# sch_arduboy.net
KiCad netlist of a schematic drawn in Altium Designer
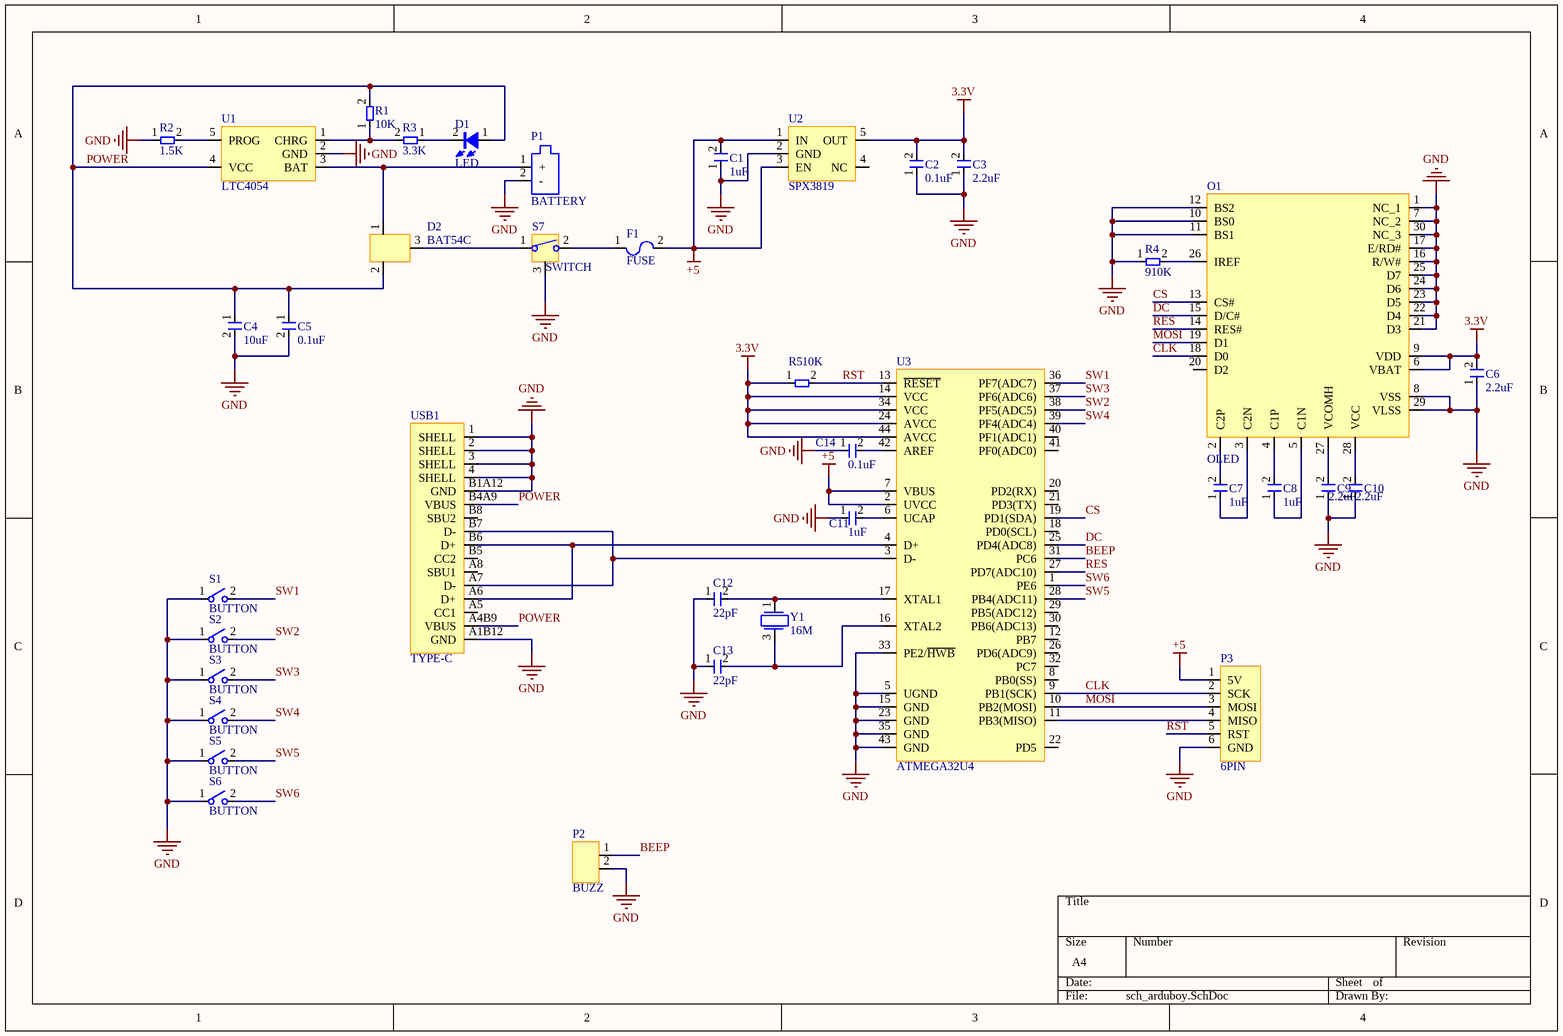
[diagram p0: sch_arduboy.SchDoc]

(export (version "E")
  (design (tool "Eeschema 10.0.6"))
  (components
    (comp (ref "C1")
      (value "1uF")
      (footprint "CAP0603")
      (description "CAP")
      (libsource (lib "arduboy_schlib") (part "CAP"))
    )
    (comp (ref "C2")
      (value "0.1uF")
      (footprint "CAP0603")
      (description "CAP")
      (libsource (lib "arduboy_schlib") (part "CAP"))
    )
    (comp (ref "C3")
      (value "2.2uF")
      (footprint "CAP0603")
      (description "CAP")
      (libsource (lib "arduboy_schlib") (part "CAP"))
    )
    (comp (ref "C4")
      (value "10uF")
      (footprint "10uFCAP3216")
      (description "CAP")
      (libsource (lib "arduboy_schlib") (part "CAP"))
    )
    (comp (ref "C5")
      (value "0.1uF")
      (footprint "CAP0603")
      (description "CAP")
      (libsource (lib "arduboy_schlib") (part "CAP"))
    )
    (comp (ref "C6")
      (value "2.2uF")
      (footprint "CAP0603")
      (description "CAP")
      (libsource (lib "arduboy_schlib") (part "CAP"))
    )
    (comp (ref "C7")
      (value "1uF")
      (footprint "CAP0603")
      (description "CAP")
      (libsource (lib "arduboy_schlib") (part "CAP"))
    )
    (comp (ref "C8")
      (value "1uF")
      (footprint "CAP0603")
      (description "CAP")
      (libsource (lib "arduboy_schlib") (part "CAP"))
    )
    (comp (ref "C9")
      (value "2.2uF")
      (footprint "CAP0603")
      (description "CAP")
      (libsource (lib "arduboy_schlib") (part "CAP"))
    )
    (comp (ref "C10")
      (value "2.2uF")
      (footprint "CAP0603")
      (description "CAP")
      (libsource (lib "arduboy_schlib") (part "CAP"))
    )
    (comp (ref "C11")
      (value "1uF")
      (footprint "CAP0603")
      (description "CAP")
      (libsource (lib "arduboy_schlib") (part "CAP"))
    )
    (comp (ref "C12")
      (value "22pF")
      (footprint "CAP0603")
      (description "CAP")
      (libsource (lib "arduboy_schlib") (part "CAP"))
    )
    (comp (ref "C13")
      (value "22pF")
      (footprint "CAP0603")
      (description "CAP")
      (libsource (lib "arduboy_schlib") (part "CAP"))
    )
    (comp (ref "C14")
      (value "0.1uF")
      (footprint "CAP0603")
      (description "CAP")
      (libsource (lib "arduboy_schlib") (part "CAP"))
    )
    (comp (ref "D1") (value "LED") (footprint "LED0603") (libsource (lib "arduboy_schlib") (part "LED")))
    (comp (ref "D2")
      (value "BAT54C")
      (footprint "BAT54CSOT23-3")
      (libsource (lib "arduboy_schlib") (part "BAT54C"))
    )
    (comp (ref "F1") (value "FUSE") (footprint "FUSE1206") (libsource (lib "arduboy_schlib") (part "FUSE")))
    (comp (ref "O1")
      (value "OLED")
      (footprint "OLED30P")
      (description "0.96 128x64OLED")
      (libsource (lib "arduboy_schlib") (part "OLED"))
    )
    (comp (ref "P1")
      (value "BATTERY")
      (footprint "BATTERY")
      (libsource (lib "arduboy_schlib") (part "BATTERY"))
    )
    (comp (ref "P2") (value "BUZZ") (footprint "BUZZ") (libsource (lib "arduboy_schlib") (part "BUZZ")))
    (comp (ref "P3") (value "6PIN") (footprint "6PIN254") (libsource (lib "arduboy_schlib") (part "6PIN")))
    (comp (ref "R1")
      (value "10K")
      (footprint "RES0805")
      (description "电阻")
      (libsource (lib "arduboy_schlib") (part "RES"))
    )
    (comp (ref "R2")
      (value "1.5K")
      (footprint "RES0805")
      (description "电阻")
      (libsource (lib "arduboy_schlib") (part "RES"))
    )
    (comp (ref "R3")
      (value "3.3K")
      (footprint "RES0805")
      (description "电阻")
      (libsource (lib "arduboy_schlib") (part "RES"))
    )
    (comp (ref "R4")
      (value "910K")
      (footprint "RES0805")
      (description "电阻")
      (libsource (lib "arduboy_schlib") (part "RES"))
    )
    (comp (ref "R5")
      (value "10K")
      (footprint "RES0805")
      (description "电阻")
      (libsource (lib "arduboy_schlib") (part "RES"))
    )
    (comp (ref "S1")
      (value "BUTTON")
      (footprint "SKP_BUTTON")
      (libsource (lib "arduboy_schlib") (part "BUTTON"))
    )
    (comp (ref "S2")
      (value "BUTTON")
      (footprint "SKP_BUTTON")
      (libsource (lib "arduboy_schlib") (part "BUTTON"))
    )
    (comp (ref "S3")
      (value "BUTTON")
      (footprint "SKP_BUTTON")
      (libsource (lib "arduboy_schlib") (part "BUTTON"))
    )
    (comp (ref "S4")
      (value "BUTTON")
      (footprint "SKP_BUTTON")
      (libsource (lib "arduboy_schlib") (part "BUTTON"))
    )
    (comp (ref "S5")
      (value "BUTTON")
      (footprint "SKP_BUTTON")
      (libsource (lib "arduboy_schlib") (part "BUTTON"))
    )
    (comp (ref "S6")
      (value "BUTTON")
      (footprint "SKP_BUTTON")
      (libsource (lib "arduboy_schlib") (part "BUTTON"))
    )
    (comp (ref "S7")
      (value "SWITCH")
      (footprint "SWITCH_BUTTON")
      (libsource (lib "arduboy_schlib") (part "SWITCH"))
    )
    (comp (ref "U1")
      (value "LTC4054")
      (footprint "LTC4054")
      (libsource (lib "arduboy_schlib") (part "LTC4054"))
    )
    (comp (ref "U2")
      (value "SPX3819")
      (footprint "SPX3819")
      (libsource (lib "arduboy_schlib") (part "SPX3819"))
    )
    (comp (ref "U3")
      (value "ATMEGA32U4")
      (footprint "ATMEGA32U4AU")
      (libsource (lib "arduboy_schlib") (part "ATMEGA32U4"))
    )
    (comp (ref "USB1")
      (value "TYPE-C")
      (footprint "TYPE-C")
      (libsource (lib "arduboy_schlib") (part "TYPE-C"))
    )
    (comp (ref "Y1")
      (value "16M")
      (footprint "CRYSTAL")
      (description "CRYSTAL")
      (libsource (lib "arduboy_schlib") (part "CRYSTAL"))
    )
  )
  (nets
    (net (code "1") (name "+5") (class "Default")
      (node (ref "C1") (pin "2") (pinfunction "2_2") (pintype "passive"))
      (node (ref "F1") (pin "2") (pinfunction "2_2") (pintype "passive"))
      (node (ref "P3") (pin "1") (pinfunction "5V_1") (pintype "passive"))
      (node (ref "U2") (pin "1") (pinfunction "IN_1") (pintype "passive"))
      (node (ref "U2") (pin "3") (pinfunction "EN_3") (pintype "passive"))
      (node (ref "U3") (pin "2") (pinfunction "UVCC_2") (pintype "passive"))
      (node (ref "U3") (pin "7") (pinfunction "VBUS_7") (pintype "passive"))
    )
    (net (code "2") (name "/BEEP") (class "Default")
      (node (ref "P2") (pin "1") (pinfunction "1_1") (pintype "passive"))
      (node (ref "U3") (pin "31") (pinfunction "PC6_31") (pintype "passive"))
    )
    (net (code "3") (name "/CLK") (class "Default")
      (node (ref "O1") (pin "18") (pinfunction "D0_18") (pintype "passive"))
      (node (ref "P3") (pin "2") (pinfunction "SCK_2") (pintype "passive"))
      (node (ref "U3") (pin "9") (pinfunction "PB1(SCK)_9") (pintype "passive"))
    )
    (net (code "4") (name "/CS") (class "Default")
      (node (ref "O1") (pin "13") (pinfunction "CS#_13") (pintype "passive"))
      (node (ref "U3") (pin "19") (pinfunction "PD1(SDA)_19") (pintype "passive"))
    )
    (net (code "5") (name "/DC") (class "Default")
      (node (ref "O1") (pin "15") (pinfunction "D/C#_15") (pintype "passive"))
      (node (ref "U3") (pin "25") (pinfunction "PD4(ADC8)_25") (pintype "passive"))
    )
    (net (code "6") (name "/MOSI") (class "Default")
      (node (ref "O1") (pin "19") (pinfunction "D1_19") (pintype "passive"))
      (node (ref "P3") (pin "3") (pinfunction "MOSI_3") (pintype "passive"))
      (node (ref "U3") (pin "10") (pinfunction "PB2(MOSI)_10") (pintype "passive"))
    )
    (net (code "7") (name "/POWER") (class "Default")
      (node (ref "C4") (pin "1") (pinfunction "1_1") (pintype "passive"))
      (node (ref "C5") (pin "1") (pinfunction "1_1") (pintype "passive"))
      (node (ref "D1") (pin "1") (pinfunction "1_1") (pintype "passive"))
      (node (ref "D2") (pin "2") (pinfunction "2_2") (pintype "passive"))
      (node (ref "R1") (pin "2") (pinfunction "2_2") (pintype "passive"))
      (node (ref "U1") (pin "4") (pinfunction "VCC_4") (pintype "passive"))
      (node (ref "USB1") (pin "A4B9") (pinfunction "VBUS_A4B9") (pintype "passive"))
      (node (ref "USB1") (pin "B4A9") (pinfunction "VBUS_B4A9") (pintype "passive"))
    )
    (net (code "8") (name "/RES") (class "Default")
      (node (ref "O1") (pin "14") (pinfunction "RES#_14") (pintype "passive"))
      (node (ref "U3") (pin "27") (pinfunction "PD7(ADC10)_27") (pintype "passive"))
    )
    (net (code "9") (name "/RST") (class "Default")
      (node (ref "P3") (pin "5") (pinfunction "RST_5") (pintype "passive"))
      (node (ref "R5") (pin "2") (pinfunction "2_2") (pintype "passive"))
      (node (ref "U3") (pin "13") (pinfunction "~{RESET}_13") (pintype "passive"))
    )
    (net (code "10") (name "/SW1") (class "Default")
      (node (ref "S1") (pin "2") (pinfunction "2_2") (pintype "passive"))
      (node (ref "U3") (pin "36") (pinfunction "PF7(ADC7)_36") (pintype "passive"))
    )
    (net (code "11") (name "/SW2") (class "Default")
      (node (ref "S2") (pin "2") (pinfunction "2_2") (pintype "passive"))
      (node (ref "U3") (pin "38") (pinfunction "PF5(ADC5)_38") (pintype "passive"))
    )
    (net (code "12") (name "/SW3") (class "Default")
      (node (ref "S3") (pin "2") (pinfunction "2_2") (pintype "passive"))
      (node (ref "U3") (pin "37") (pinfunction "PF6(ADC6)_37") (pintype "passive"))
    )
    (net (code "13") (name "/SW4") (class "Default")
      (node (ref "S4") (pin "2") (pinfunction "2_2") (pintype "passive"))
      (node (ref "U3") (pin "39") (pinfunction "PF4(ADC4)_39") (pintype "passive"))
    )
    (net (code "14") (name "/SW5") (class "Default")
      (node (ref "S5") (pin "2") (pinfunction "2_2") (pintype "passive"))
      (node (ref "U3") (pin "28") (pinfunction "PB4(ADC11)_28") (pintype "passive"))
    )
    (net (code "15") (name "/SW6") (class "Default")
      (node (ref "S6") (pin "2") (pinfunction "2_2") (pintype "passive"))
      (node (ref "U3") (pin "1") (pinfunction "PE6_1") (pintype "passive"))
    )
    (net (code "16") (name "3.3V") (class "Default")
      (node (ref "C2") (pin "2") (pinfunction "2_2") (pintype "passive"))
      (node (ref "C3") (pin "2") (pinfunction "2_2") (pintype "passive"))
      (node (ref "C6") (pin "2") (pinfunction "2_2") (pintype "passive"))
      (node (ref "O1") (pin "6") (pinfunction "VBAT_6") (pintype "passive"))
      (node (ref "O1") (pin "9") (pinfunction "VDD_9") (pintype "passive"))
      (node (ref "R5") (pin "1") (pinfunction "1_1") (pintype "passive"))
      (node (ref "U2") (pin "5") (pinfunction "OUT_5") (pintype "passive"))
      (node (ref "U3") (pin "14") (pinfunction "VCC_14") (pintype "passive"))
      (node (ref "U3") (pin "24") (pinfunction "AVCC_24") (pintype "passive"))
      (node (ref "U3") (pin "34") (pinfunction "VCC_34") (pintype "passive"))
      (node (ref "U3") (pin "44") (pinfunction "AVCC_44") (pintype "passive"))
    )
    (net (code "17") (name "GND") (class "Default")
      (node (ref "C1") (pin "1") (pinfunction "1_1") (pintype "passive"))
      (node (ref "C10") (pin "1") (pinfunction "1_1") (pintype "passive"))
      (node (ref "C11") (pin "1") (pinfunction "1_1") (pintype "passive"))
      (node (ref "C12") (pin "1") (pinfunction "1_1") (pintype "passive"))
      (node (ref "C13") (pin "1") (pinfunction "1_1") (pintype "passive"))
      (node (ref "C14") (pin "1") (pinfunction "1_1") (pintype "passive"))
      (node (ref "C2") (pin "1") (pinfunction "1_1") (pintype "passive"))
      (node (ref "C3") (pin "1") (pinfunction "1_1") (pintype "passive"))
      (node (ref "C4") (pin "2") (pinfunction "2_2") (pintype "passive"))
      (node (ref "C5") (pin "2") (pinfunction "2_2") (pintype "passive"))
      (node (ref "C6") (pin "1") (pinfunction "1_1") (pintype "passive"))
      (node (ref "C9") (pin "1") (pinfunction "1_1") (pintype "passive"))
      (node (ref "O1") (pin "1") (pinfunction "NC_1_1") (pintype "passive"))
      (node (ref "O1") (pin "10") (pinfunction "BS0_10") (pintype "passive"))
      (node (ref "O1") (pin "11") (pinfunction "BS1_11") (pintype "passive"))
      (node (ref "O1") (pin "12") (pinfunction "BS2_12") (pintype "passive"))
      (node (ref "O1") (pin "16") (pinfunction "R/W#_16") (pintype "passive"))
      (node (ref "O1") (pin "17") (pinfunction "E/RD#_17") (pintype "passive"))
      (node (ref "O1") (pin "21") (pinfunction "D3_21") (pintype "passive"))
      (node (ref "O1") (pin "22") (pinfunction "D4_22") (pintype "passive"))
      (node (ref "O1") (pin "23") (pinfunction "D5_23") (pintype "passive"))
      (node (ref "O1") (pin "24") (pinfunction "D6_24") (pintype "passive"))
      (node (ref "O1") (pin "25") (pinfunction "D7_25") (pintype "passive"))
      (node (ref "O1") (pin "29") (pinfunction "VLSS_29") (pintype "passive"))
      (node (ref "O1") (pin "30") (pinfunction "NC_3_30") (pintype "passive"))
      (node (ref "O1") (pin "7") (pinfunction "NC_2_7") (pintype "passive"))
      (node (ref "O1") (pin "8") (pinfunction "VSS_8") (pintype "passive"))
      (node (ref "P1") (pin "2") (pinfunction "-_2") (pintype "passive"))
      (node (ref "P2") (pin "2") (pinfunction "2_2") (pintype "passive"))
      (node (ref "P3") (pin "6") (pinfunction "GND_6") (pintype "passive"))
      (node (ref "R2") (pin "1") (pinfunction "1_1") (pintype "passive"))
      (node (ref "R4") (pin "1") (pinfunction "1_1") (pintype "passive"))
      (node (ref "S1") (pin "1") (pinfunction "1_1") (pintype "passive"))
      (node (ref "S2") (pin "1") (pinfunction "1_1") (pintype "passive"))
      (node (ref "S3") (pin "1") (pinfunction "1_1") (pintype "passive"))
      (node (ref "S4") (pin "1") (pinfunction "1_1") (pintype "passive"))
      (node (ref "S5") (pin "1") (pinfunction "1_1") (pintype "passive"))
      (node (ref "S6") (pin "1") (pinfunction "1_1") (pintype "passive"))
      (node (ref "S7") (pin "3") (pinfunction "3_3") (pintype "passive"))
      (node (ref "U1") (pin "2") (pinfunction "GND_2") (pintype "passive"))
      (node (ref "U2") (pin "2") (pinfunction "GND_2") (pintype "passive"))
      (node (ref "U3") (pin "15") (pinfunction "GND_15") (pintype "passive"))
      (node (ref "U3") (pin "23") (pinfunction "GND_23") (pintype "passive"))
      (node (ref "U3") (pin "33") (pinfunction "PE2/~{HWB}_33") (pintype "passive"))
      (node (ref "U3") (pin "35") (pinfunction "GND_35") (pintype "passive"))
      (node (ref "U3") (pin "43") (pinfunction "GND_43") (pintype "passive"))
      (node (ref "U3") (pin "5") (pinfunction "UGND_5") (pintype "passive"))
      (node (ref "USB1") (pin "1") (pinfunction "SHELL_1") (pintype "passive"))
      (node (ref "USB1") (pin "2") (pinfunction "SHELL_2") (pintype "passive"))
      (node (ref "USB1") (pin "3") (pinfunction "SHELL_3") (pintype "passive"))
      (node (ref "USB1") (pin "4") (pinfunction "SHELL_4") (pintype "passive"))
      (node (ref "USB1") (pin "A1B12") (pinfunction "GND_A1B12") (pintype "passive"))
      (node (ref "USB1") (pin "B1A12") (pinfunction "GND_B1A12") (pintype "passive"))
    )
    (net (code "18") (name "Net-(D1-Pad2)") (class "Default")
      (node (ref "D1") (pin "2") (pinfunction "2_2") (pintype "passive"))
      (node (ref "R3") (pin "1") (pinfunction "1_1") (pintype "passive"))
    )
    (net (code "19") (name "Net-(D2-Pad3)") (class "Default")
      (node (ref "D2") (pin "3") (pinfunction "3_3") (pintype "passive"))
      (node (ref "S7") (pin "1") (pinfunction "1_1") (pintype "passive"))
    )
    (net (code "20") (name "Net-(F1-Pad1)") (class "Default")
      (node (ref "F1") (pin "1") (pinfunction "1_1") (pintype "passive"))
      (node (ref "S7") (pin "2") (pinfunction "2_2") (pintype "passive"))
    )
    (net (code "21") (name "Net-(O1-C1N)") (class "Default")
      (node (ref "C8") (pin "1") (pinfunction "1_1") (pintype "passive"))
      (node (ref "O1") (pin "5") (pinfunction "C1N_5") (pintype "passive"))
    )
    (net (code "22") (name "Net-(O1-C1P)") (class "Default")
      (node (ref "C8") (pin "2") (pinfunction "2_2") (pintype "passive"))
      (node (ref "O1") (pin "4") (pinfunction "C1P_4") (pintype "passive"))
    )
    (net (code "23") (name "Net-(O1-C2N)") (class "Default")
      (node (ref "C7") (pin "1") (pinfunction "1_1") (pintype "passive"))
      (node (ref "O1") (pin "3") (pinfunction "C2N_3") (pintype "passive"))
    )
    (net (code "24") (name "Net-(O1-C2P)") (class "Default")
      (node (ref "C7") (pin "2") (pinfunction "2_2") (pintype "passive"))
      (node (ref "O1") (pin "2") (pinfunction "C2P_2") (pintype "passive"))
    )
    (net (code "25") (name "Net-(O1-IREF)") (class "Default")
      (node (ref "O1") (pin "26") (pinfunction "IREF_26") (pintype "passive"))
      (node (ref "R4") (pin "2") (pinfunction "2_2") (pintype "passive"))
    )
    (net (code "26") (name "Net-(O1-VCC)") (class "Default")
      (node (ref "C10") (pin "2") (pinfunction "2_2") (pintype "passive"))
      (node (ref "O1") (pin "28") (pinfunction "VCC_28") (pintype "passive"))
    )
    (net (code "27") (name "Net-(O1-VCOMH)") (class "Default")
      (node (ref "C9") (pin "2") (pinfunction "2_2") (pintype "passive"))
      (node (ref "O1") (pin "27") (pinfunction "VCOMH_27") (pintype "passive"))
    )
    (net (code "28") (name "Net-(P1-+)") (class "Default")
      (node (ref "D2") (pin "1") (pinfunction "1_1") (pintype "passive"))
      (node (ref "P1") (pin "1") (pinfunction "+_1") (pintype "passive"))
      (node (ref "U1") (pin "3") (pinfunction "BAT_3") (pintype "passive"))
    )
    (net (code "29") (name "Net-(P3-MISO)") (class "Default")
      (node (ref "P3") (pin "4") (pinfunction "MISO_4") (pintype "passive"))
      (node (ref "U3") (pin "11") (pinfunction "PB3(MISO)_11") (pintype "passive"))
    )
    (net (code "30") (name "Net-(U1-CHRG)") (class "Default")
      (node (ref "R1") (pin "1") (pinfunction "1_1") (pintype "passive"))
      (node (ref "R3") (pin "2") (pinfunction "2_2") (pintype "passive"))
      (node (ref "U1") (pin "1") (pinfunction "CHRG_1") (pintype "passive"))
    )
    (net (code "31") (name "Net-(U1-PROG)") (class "Default")
      (node (ref "R2") (pin "2") (pinfunction "2_2") (pintype "passive"))
      (node (ref "U1") (pin "5") (pinfunction "PROG_5") (pintype "passive"))
    )
    (net (code "32") (name "Net-(U3-AREF)") (class "Default")
      (node (ref "C14") (pin "2") (pinfunction "2_2") (pintype "passive"))
      (node (ref "U3") (pin "42") (pinfunction "AREF_42") (pintype "passive"))
    )
    (net (code "33") (name "Net-(U3-D+)") (class "Default")
      (node (ref "U3") (pin "4") (pinfunction "D+_4") (pintype "passive"))
      (node (ref "USB1") (pin "A6") (pinfunction "D+_A6") (pintype "passive"))
      (node (ref "USB1") (pin "B6") (pinfunction "D+_B6") (pintype "passive"))
    )
    (net (code "34") (name "Net-(U3-D-)") (class "Default")
      (node (ref "U3") (pin "3") (pinfunction "D-_3") (pintype "passive"))
      (node (ref "USB1") (pin "A7") (pinfunction "D-_A7") (pintype "passive"))
      (node (ref "USB1") (pin "B7") (pinfunction "D-_B7") (pintype "passive"))
    )
    (net (code "35") (name "Net-(U3-UCAP)") (class "Default")
      (node (ref "C11") (pin "2") (pinfunction "2_2") (pintype "passive"))
      (node (ref "U3") (pin "6") (pinfunction "UCAP_6") (pintype "passive"))
    )
    (net (code "36") (name "Net-(U3-XTAL1)") (class "Default")
      (node (ref "C12") (pin "2") (pinfunction "2_2") (pintype "passive"))
      (node (ref "U3") (pin "17") (pinfunction "XTAL1_17") (pintype "passive"))
      (node (ref "Y1") (pin "1") (pinfunction "1_1") (pintype "passive"))
    )
    (net (code "37") (name "Net-(U3-XTAL2)") (class "Default")
      (node (ref "C13") (pin "2") (pinfunction "2_2") (pintype "passive"))
      (node (ref "U3") (pin "16") (pinfunction "XTAL2_16") (pintype "passive"))
      (node (ref "Y1") (pin "3") (pinfunction "3_3") (pintype "passive"))
    )
    (net (code "38") (name "unconnected-(O1-D2-Pad20)") (class "Default")
      (node (ref "O1") (pin "20") (pinfunction "D2_20") (pintype "passive"))
    )
    (net (code "39") (name "unconnected-(U2-NC-Pad4)") (class "Default")
      (node (ref "U2") (pin "4") (pinfunction "NC_4") (pintype "passive"))
    )
    (net (code "40") (name "unconnected-(U3-PB0(SS)-Pad8)") (class "Default")
      (node (ref "U3") (pin "8") (pinfunction "PB0(SS)_8") (pintype "passive"))
    )
    (net (code "41") (name "unconnected-(U3-PB5(ADC12)-Pad29)") (class "Default")
      (node (ref "U3") (pin "29") (pinfunction "PB5(ADC12)_29") (pintype "passive"))
    )
    (net (code "42") (name "unconnected-(U3-PB6(ADC13)-Pad30)") (class "Default")
      (node (ref "U3") (pin "30") (pinfunction "PB6(ADC13)_30") (pintype "passive"))
    )
    (net (code "43") (name "unconnected-(U3-PB7-Pad12)") (class "Default")
      (node (ref "U3") (pin "12") (pinfunction "PB7_12") (pintype "passive"))
    )
    (net (code "44") (name "unconnected-(U3-PC7-Pad32)") (class "Default")
      (node (ref "U3") (pin "32") (pinfunction "PC7_32") (pintype "passive"))
    )
    (net (code "45") (name "unconnected-(U3-PD0(SCL)-Pad18)") (class "Default")
      (node (ref "U3") (pin "18") (pinfunction "PD0(SCL)_18") (pintype "passive"))
    )
    (net (code "46") (name "unconnected-(U3-PD2(RX)-Pad20)") (class "Default")
      (node (ref "U3") (pin "20") (pinfunction "PD2(RX)_20") (pintype "passive"))
    )
    (net (code "47") (name "unconnected-(U3-PD3(TX)-Pad21)") (class "Default")
      (node (ref "U3") (pin "21") (pinfunction "PD3(TX)_21") (pintype "passive"))
    )
    (net (code "48") (name "unconnected-(U3-PD5-Pad22)") (class "Default")
      (node (ref "U3") (pin "22") (pinfunction "PD5_22") (pintype "passive"))
    )
    (net (code "49") (name "unconnected-(U3-PD6(ADC9)-Pad26)") (class "Default")
      (node (ref "U3") (pin "26") (pinfunction "PD6(ADC9)_26") (pintype "passive"))
    )
    (net (code "50") (name "unconnected-(U3-PF0(ADC0)-Pad41)") (class "Default")
      (node (ref "U3") (pin "41") (pinfunction "PF0(ADC0)_41") (pintype "passive"))
    )
    (net (code "51") (name "unconnected-(U3-PF1(ADC1)-Pad40)") (class "Default")
      (node (ref "U3") (pin "40") (pinfunction "PF1(ADC1)_40") (pintype "passive"))
    )
    (net (code "52") (name "unconnected-(USB1-CC1-PadA5)") (class "Default")
      (node (ref "USB1") (pin "A5") (pinfunction "CC1_A5") (pintype "passive"))
    )
    (net (code "53") (name "unconnected-(USB1-CC2-PadB5)") (class "Default")
      (node (ref "USB1") (pin "B5") (pinfunction "CC2_B5") (pintype "passive"))
    )
    (net (code "54") (name "unconnected-(USB1-SBU1-PadA8)") (class "Default")
      (node (ref "USB1") (pin "A8") (pinfunction "SBU1_A8") (pintype "passive"))
    )
    (net (code "55") (name "unconnected-(USB1-SBU2-PadB8)") (class "Default")
      (node (ref "USB1") (pin "B8") (pinfunction "SBU2_B8") (pintype "passive"))
    )
  )
)
